# NanoBase_L293D_DBL.net
KiCad netlist of a schematic drawn in EAGLE
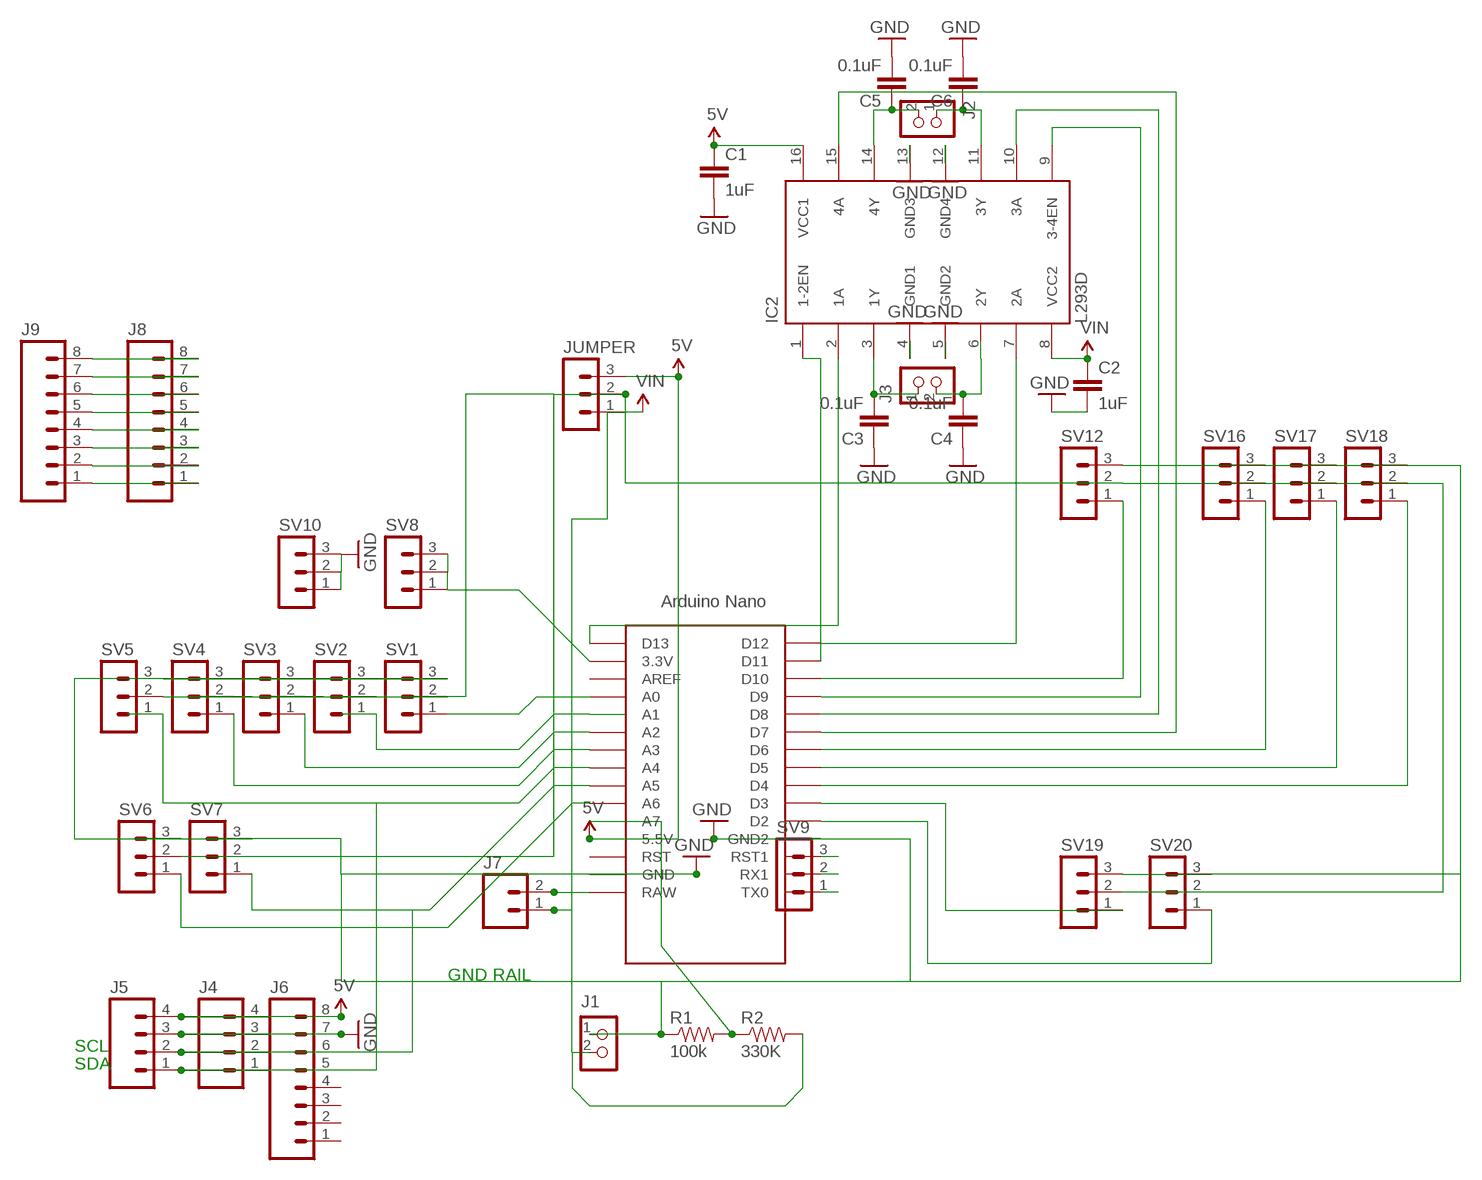
[diagram p0: schematic, sheet 1]

(export (version "E")
  (design (tool "Eeschema 10.0.6"))
  (components
    (comp (ref "C1")
      (value "1uF")
      (footprint "eagle-import:1206")
      (libsource (lib "eagle-import") (part "2.2UF-CERCAP-10009"))
    )
    (comp (ref "C2")
      (value "1uF")
      (footprint "eagle-import:1206")
      (libsource (lib "eagle-import") (part "2.2UF-CERCAP-10009"))
    )
    (comp (ref "C3")
      (value "0.1uF")
      (footprint "eagle-import:1206")
      (libsource (lib "eagle-import") (part "2.2UF-CERCAP-10009"))
    )
    (comp (ref "C4")
      (value "0.1uF")
      (footprint "eagle-import:1206")
      (libsource (lib "eagle-import") (part "2.2UF-CERCAP-10009"))
    )
    (comp (ref "C5")
      (value "0.1uF")
      (footprint "eagle-import:1206")
      (libsource (lib "eagle-import") (part "2.2UF-CERCAP-10009"))
    )
    (comp (ref "C6")
      (value "0.1uF")
      (footprint "eagle-import:1206")
      (libsource (lib "eagle-import") (part "2.2UF-CERCAP-10009"))
    )
    (comp (ref "IC2")
      (value "L293D")
      (footprint "eagle-import:DIL16")
      (libsource (lib "eagle-import") (part "L293D"))
    )
    (comp (ref "J1")
      (value "CON_TERMINAL_BLOCK_02-5MM")
      (footprint "eagle-import:TERMINAL_BLOCK_2P_5")
      (libsource (lib "eagle-import") (part "CON_TERMINAL_BLOCK_02-5MM"))
    )
    (comp (ref "J2")
      (value "CON_TERMINAL_BLOCK_02-5MM")
      (footprint "eagle-import:TERMINAL_BLOCK_2P_5")
      (libsource (lib "eagle-import") (part "CON_TERMINAL_BLOCK_02-5MM"))
    )
    (comp (ref "J3")
      (value "CON_TERMINAL_BLOCK_02-5MM")
      (footprint "eagle-import:TERMINAL_BLOCK_2P_5")
      (libsource (lib "eagle-import") (part "CON_TERMINAL_BLOCK_02-5MM"))
    )
    (comp (ref "J4")
      (value "M04LOCK")
      (footprint "eagle-import:1X04_LOCK")
      (libsource (lib "eagle-import") (part "M04LOCK"))
    )
    (comp (ref "J5")
      (value "M04LOCK")
      (footprint "eagle-import:1X04_LOCK")
      (libsource (lib "eagle-import") (part "M04LOCK"))
    )
    (comp (ref "J6")
      (value "M08NO_SILK")
      (footprint "eagle-import:1X08_PIN1_NO_SILK")
      (libsource (lib "eagle-import") (part "M08NO_SILK"))
    )
    (comp (ref "J7")
      (value "M02LOCK_LONGPADS")
      (footprint "eagle-import:1X02_LOCK_LONGPADS")
      (libsource (lib "eagle-import") (part "M02LOCK_LONGPADS"))
    )
    (comp (ref "J8")
      (value "M08NO_SILK")
      (footprint "eagle-import:1X08_PIN1_NO_SILK")
      (libsource (lib "eagle-import") (part "M08NO_SILK"))
    )
    (comp (ref "J9")
      (value "M08NO_SILK")
      (footprint "eagle-import:1X08_PIN1_NO_SILK")
      (libsource (lib "eagle-import") (part "M08NO_SILK"))
    )
    (comp (ref "JUMPER")
      (value "MA03-1")
      (footprint "eagle-import:MA03-1")
      (libsource (lib "eagle-import") (part "MA03-1"))
    )
    (comp (ref "R1")
      (value "100k")
      (footprint "eagle-import:1206")
      (libsource (lib "eagle-import") (part "RESISTOR1206"))
    )
    (comp (ref "R2")
      (value "330K")
      (footprint "eagle-import:1206")
      (libsource (lib "eagle-import") (part "RESISTOR1206"))
    )
    (comp (ref "SV1")
      (value "MA03-1")
      (footprint "eagle-import:MA03-1")
      (libsource (lib "eagle-import") (part "MA03-1"))
    )
    (comp (ref "SV2")
      (value "MA03-1")
      (footprint "eagle-import:MA03-1")
      (libsource (lib "eagle-import") (part "MA03-1"))
    )
    (comp (ref "SV3")
      (value "MA03-1")
      (footprint "eagle-import:MA03-1")
      (libsource (lib "eagle-import") (part "MA03-1"))
    )
    (comp (ref "SV4")
      (value "MA03-1")
      (footprint "eagle-import:MA03-1")
      (libsource (lib "eagle-import") (part "MA03-1"))
    )
    (comp (ref "SV5")
      (value "MA03-1")
      (footprint "eagle-import:MA03-1")
      (libsource (lib "eagle-import") (part "MA03-1"))
    )
    (comp (ref "SV6")
      (value "MA03-1")
      (footprint "eagle-import:MA03-1")
      (libsource (lib "eagle-import") (part "MA03-1"))
    )
    (comp (ref "SV7")
      (value "MA03-1")
      (footprint "eagle-import:MA03-1")
      (libsource (lib "eagle-import") (part "MA03-1"))
    )
    (comp (ref "SV8")
      (value "MA03-1")
      (footprint "eagle-import:MA03-1")
      (libsource (lib "eagle-import") (part "MA03-1"))
    )
    (comp (ref "SV9")
      (value "MA03-1")
      (footprint "eagle-import:MA03-1")
      (libsource (lib "eagle-import") (part "MA03-1"))
    )
    (comp (ref "SV10")
      (value "MA03-1")
      (footprint "eagle-import:MA03-1")
      (libsource (lib "eagle-import") (part "MA03-1"))
    )
    (comp (ref "SV12")
      (value "MA03-1")
      (footprint "eagle-import:MA03-1")
      (libsource (lib "eagle-import") (part "MA03-1"))
    )
    (comp (ref "SV16")
      (value "MA03-1")
      (footprint "eagle-import:MA03-1")
      (libsource (lib "eagle-import") (part "MA03-1"))
    )
    (comp (ref "SV17")
      (value "MA03-1")
      (footprint "eagle-import:MA03-1")
      (libsource (lib "eagle-import") (part "MA03-1"))
    )
    (comp (ref "SV18")
      (value "MA03-1")
      (footprint "eagle-import:MA03-1")
      (libsource (lib "eagle-import") (part "MA03-1"))
    )
    (comp (ref "SV19")
      (value "MA03-1")
      (footprint "eagle-import:MA03-1")
      (libsource (lib "eagle-import") (part "MA03-1"))
    )
    (comp (ref "SV20")
      (value "MA03-1")
      (footprint "eagle-import:MA03-1")
      (libsource (lib "eagle-import") (part "MA03-1"))
    )
    (comp (ref "U$1")
      (value "NANO")
      (footprint "eagle-import:NANO")
      (libsource (lib "eagle-import") (part "NANO"))
    )
  )
  (nets
    (net (code "1") (name "5V") (class "Default")
      (node (ref "C1") (pin "1") (pinfunction "1_1") (pintype "passive"))
      (node (ref "IC2") (pin "16") (pinfunction "VCC1_16") (pintype "power_in"))
      (node (ref "J4") (pin "4") (pinfunction "4_4") (pintype "passive"))
      (node (ref "J5") (pin "4") (pinfunction "4_4") (pintype "passive"))
      (node (ref "J6") (pin "8") (pinfunction "8_8") (pintype "passive"))
      (node (ref "JUMPER") (pin "3") (pinfunction "3_3") (pintype "passive"))
      (node (ref "U$1") (pin "5V") (pinfunction "5.5V_5V") (pintype "bidirectional"))
    )
    (net (code "2") (name "GND") (class "Default")
      (node (ref "C1") (pin "2") (pinfunction "2_2") (pintype "passive"))
      (node (ref "C2") (pin "2") (pinfunction "2_2") (pintype "passive"))
      (node (ref "C3") (pin "1") (pinfunction "1_1") (pintype "passive"))
      (node (ref "C4") (pin "1") (pinfunction "1_1") (pintype "passive"))
      (node (ref "C5") (pin "2") (pinfunction "2_2") (pintype "passive"))
      (node (ref "C6") (pin "2") (pinfunction "2_2") (pintype "passive"))
      (node (ref "IC2") (pin "12") (pinfunction "GND4_12") (pintype "power_in"))
      (node (ref "IC2") (pin "13") (pinfunction "GND3_13") (pintype "power_in"))
      (node (ref "IC2") (pin "4") (pinfunction "GND1_4") (pintype "power_in"))
      (node (ref "IC2") (pin "5") (pinfunction "GND2_5") (pintype "power_in"))
      (node (ref "J1") (pin "1") (pinfunction "1_1") (pintype "passive"))
      (node (ref "J4") (pin "3") (pinfunction "3_3") (pintype "passive"))
      (node (ref "J5") (pin "3") (pinfunction "3_3") (pintype "passive"))
      (node (ref "J6") (pin "7") (pinfunction "7_7") (pintype "passive"))
      (node (ref "R1") (pin "1") (pinfunction "1_1") (pintype "passive"))
      (node (ref "SV1") (pin "3") (pinfunction "3_3") (pintype "passive"))
      (node (ref "SV10") (pin "1") (pinfunction "1_1") (pintype "passive"))
      (node (ref "SV10") (pin "2") (pinfunction "2_2") (pintype "passive"))
      (node (ref "SV10") (pin "3") (pinfunction "3_3") (pintype "passive"))
      (node (ref "SV12") (pin "3") (pinfunction "3_3") (pintype "passive"))
      (node (ref "SV16") (pin "3") (pinfunction "3_3") (pintype "passive"))
      (node (ref "SV17") (pin "3") (pinfunction "3_3") (pintype "passive"))
      (node (ref "SV18") (pin "3") (pinfunction "3_3") (pintype "passive"))
      (node (ref "SV19") (pin "3") (pinfunction "3_3") (pintype "passive"))
      (node (ref "SV2") (pin "3") (pinfunction "3_3") (pintype "passive"))
      (node (ref "SV20") (pin "3") (pinfunction "3_3") (pintype "passive"))
      (node (ref "SV3") (pin "3") (pinfunction "3_3") (pintype "passive"))
      (node (ref "SV4") (pin "3") (pinfunction "3_3") (pintype "passive"))
      (node (ref "SV5") (pin "3") (pinfunction "3_3") (pintype "passive"))
      (node (ref "SV6") (pin "3") (pinfunction "3_3") (pintype "passive"))
      (node (ref "SV7") (pin "3") (pinfunction "3_3") (pintype "passive"))
      (node (ref "U$1") (pin "GND") (pinfunction "GND_GND") (pintype "bidirectional"))
      (node (ref "U$1") (pin "GND1") (pinfunction "GND2_GND1") (pintype "bidirectional"))
    )
    (net (code "3") (name "Net-(IC2-1-2EN)") (class "Default")
      (node (ref "IC2") (pin "1") (pinfunction "1-2EN_1") (pintype "input"))
      (node (ref "U$1") (pin "D11") (pinfunction "D11_D11") (pintype "bidirectional"))
    )
    (net (code "4") (name "Net-(IC2-1A)") (class "Default")
      (node (ref "IC2") (pin "2") (pinfunction "1A_2") (pintype "input"))
      (node (ref "U$1") (pin "D13") (pinfunction "D13_D13") (pintype "bidirectional"))
    )
    (net (code "5") (name "Net-(IC2-1Y)") (class "Default")
      (node (ref "C3") (pin "2") (pinfunction "2_2") (pintype "passive"))
      (node (ref "IC2") (pin "3") (pinfunction "1Y_3") (pintype "output"))
      (node (ref "J3") (pin "1") (pinfunction "1_1") (pintype "passive"))
    )
    (net (code "6") (name "Net-(IC2-2A)") (class "Default")
      (node (ref "IC2") (pin "7") (pinfunction "2A_7") (pintype "input"))
      (node (ref "U$1") (pin "D12") (pinfunction "D12_D12") (pintype "bidirectional"))
    )
    (net (code "7") (name "Net-(IC2-2Y)") (class "Default")
      (node (ref "C4") (pin "2") (pinfunction "2_2") (pintype "passive"))
      (node (ref "IC2") (pin "6") (pinfunction "2Y_6") (pintype "output"))
      (node (ref "J3") (pin "2") (pinfunction "2_2") (pintype "passive"))
    )
    (net (code "8") (name "Net-(IC2-3-4EN)") (class "Default")
      (node (ref "IC2") (pin "9") (pinfunction "3-4EN_9") (pintype "input"))
      (node (ref "U$1") (pin "D9") (pinfunction "D9_D9") (pintype "bidirectional"))
    )
    (net (code "9") (name "Net-(IC2-3A)") (class "Default")
      (node (ref "IC2") (pin "10") (pinfunction "3A_10") (pintype "input"))
      (node (ref "U$1") (pin "D8") (pinfunction "D8_D8") (pintype "bidirectional"))
    )
    (net (code "10") (name "Net-(IC2-3Y)") (class "Default")
      (node (ref "C6") (pin "1") (pinfunction "1_1") (pintype "passive"))
      (node (ref "IC2") (pin "11") (pinfunction "3Y_11") (pintype "output"))
      (node (ref "J2") (pin "1") (pinfunction "1_1") (pintype "passive"))
    )
    (net (code "11") (name "Net-(IC2-4A)") (class "Default")
      (node (ref "IC2") (pin "15") (pinfunction "4A_15") (pintype "input"))
      (node (ref "U$1") (pin "D7") (pinfunction "D7_D7") (pintype "bidirectional"))
    )
    (net (code "12") (name "Net-(IC2-4Y)") (class "Default")
      (node (ref "C5") (pin "1") (pinfunction "1_1") (pintype "passive"))
      (node (ref "IC2") (pin "14") (pinfunction "4Y_14") (pintype "output"))
      (node (ref "J2") (pin "2") (pinfunction "2_2") (pintype "passive"))
    )
    (net (code "13") (name "Net-(J4-Pad1)") (class "Default")
      (node (ref "J4") (pin "1") (pinfunction "1_1") (pintype "passive"))
      (node (ref "J5") (pin "1") (pinfunction "1_1") (pintype "passive"))
      (node (ref "J6") (pin "5") (pinfunction "5_5") (pintype "passive"))
      (node (ref "SV5") (pin "1") (pinfunction "1_1") (pintype "passive"))
      (node (ref "U$1") (pin "A4") (pinfunction "A4_A4") (pintype "bidirectional"))
    )
    (net (code "14") (name "Net-(J4-Pad2)") (class "Default")
      (node (ref "J4") (pin "2") (pinfunction "2_2") (pintype "passive"))
      (node (ref "J5") (pin "2") (pinfunction "2_2") (pintype "passive"))
      (node (ref "J6") (pin "6") (pinfunction "6_6") (pintype "passive"))
      (node (ref "SV7") (pin "1") (pinfunction "1_1") (pintype "passive"))
      (node (ref "U$1") (pin "A5") (pinfunction "A5_A5") (pintype "bidirectional"))
    )
    (net (code "15") (name "Net-(J7-Pad2)") (class "Default")
      (node (ref "J7") (pin "2") (pinfunction "2_2") (pintype "passive"))
      (node (ref "U$1") (pin "RAW") (pinfunction "RAW_RAW") (pintype "bidirectional"))
    )
    (net (code "16") (name "Net-(J8-Pad1)") (class "Default")
      (node (ref "J8") (pin "1") (pinfunction "1_1") (pintype "passive"))
      (node (ref "J9") (pin "1") (pinfunction "1_1") (pintype "passive"))
    )
    (net (code "17") (name "Net-(J8-Pad2)") (class "Default")
      (node (ref "J8") (pin "2") (pinfunction "2_2") (pintype "passive"))
      (node (ref "J9") (pin "2") (pinfunction "2_2") (pintype "passive"))
    )
    (net (code "18") (name "Net-(J8-Pad3)") (class "Default")
      (node (ref "J8") (pin "3") (pinfunction "3_3") (pintype "passive"))
      (node (ref "J9") (pin "3") (pinfunction "3_3") (pintype "passive"))
    )
    (net (code "19") (name "Net-(J8-Pad4)") (class "Default")
      (node (ref "J8") (pin "4") (pinfunction "4_4") (pintype "passive"))
      (node (ref "J9") (pin "4") (pinfunction "4_4") (pintype "passive"))
    )
    (net (code "20") (name "Net-(J8-Pad5)") (class "Default")
      (node (ref "J8") (pin "5") (pinfunction "5_5") (pintype "passive"))
      (node (ref "J9") (pin "5") (pinfunction "5_5") (pintype "passive"))
    )
    (net (code "21") (name "Net-(J8-Pad6)") (class "Default")
      (node (ref "J8") (pin "6") (pinfunction "6_6") (pintype "passive"))
      (node (ref "J9") (pin "6") (pinfunction "6_6") (pintype "passive"))
    )
    (net (code "22") (name "Net-(J8-Pad7)") (class "Default")
      (node (ref "J8") (pin "7") (pinfunction "7_7") (pintype "passive"))
      (node (ref "J9") (pin "7") (pinfunction "7_7") (pintype "passive"))
    )
    (net (code "23") (name "Net-(J8-Pad8)") (class "Default")
      (node (ref "J8") (pin "8") (pinfunction "8_8") (pintype "passive"))
      (node (ref "J9") (pin "8") (pinfunction "8_8") (pintype "passive"))
    )
    (net (code "24") (name "Net-(JUMPER-Pad2)") (class "Default")
      (node (ref "JUMPER") (pin "2") (pinfunction "2_2") (pintype "passive"))
      (node (ref "SV1") (pin "2") (pinfunction "2_2") (pintype "passive"))
      (node (ref "SV12") (pin "2") (pinfunction "2_2") (pintype "passive"))
      (node (ref "SV16") (pin "2") (pinfunction "2_2") (pintype "passive"))
      (node (ref "SV17") (pin "2") (pinfunction "2_2") (pintype "passive"))
      (node (ref "SV18") (pin "2") (pinfunction "2_2") (pintype "passive"))
      (node (ref "SV19") (pin "2") (pinfunction "2_2") (pintype "passive"))
      (node (ref "SV2") (pin "2") (pinfunction "2_2") (pintype "passive"))
      (node (ref "SV20") (pin "2") (pinfunction "2_2") (pintype "passive"))
      (node (ref "SV3") (pin "2") (pinfunction "2_2") (pintype "passive"))
      (node (ref "SV4") (pin "2") (pinfunction "2_2") (pintype "passive"))
      (node (ref "SV5") (pin "2") (pinfunction "2_2") (pintype "passive"))
      (node (ref "SV6") (pin "2") (pinfunction "2_2") (pintype "passive"))
      (node (ref "SV7") (pin "2") (pinfunction "2_2") (pintype "passive"))
    )
    (net (code "25") (name "Net-(R1-Pad2)") (class "Default")
      (node (ref "R1") (pin "2") (pinfunction "2_2") (pintype "passive"))
      (node (ref "R2") (pin "1") (pinfunction "1_1") (pintype "passive"))
      (node (ref "U$1") (pin "A7") (pinfunction "A7_A7") (pintype "bidirectional"))
    )
    (net (code "26") (name "Net-(SV1-Pad1)") (class "Default")
      (node (ref "SV1") (pin "1") (pinfunction "1_1") (pintype "passive"))
      (node (ref "U$1") (pin "A0") (pinfunction "A0_A0") (pintype "bidirectional"))
    )
    (net (code "27") (name "Net-(SV2-Pad1)") (class "Default")
      (node (ref "SV2") (pin "1") (pinfunction "1_1") (pintype "passive"))
      (node (ref "U$1") (pin "A1") (pinfunction "A1_A1") (pintype "bidirectional"))
    )
    (net (code "28") (name "Net-(SV3-Pad1)") (class "Default")
      (node (ref "SV3") (pin "1") (pinfunction "1_1") (pintype "passive"))
      (node (ref "U$1") (pin "A2") (pinfunction "A2_A2") (pintype "bidirectional"))
    )
    (net (code "29") (name "Net-(SV4-Pad1)") (class "Default")
      (node (ref "SV4") (pin "1") (pinfunction "1_1") (pintype "passive"))
      (node (ref "U$1") (pin "A3") (pinfunction "A3_A3") (pintype "bidirectional"))
    )
    (net (code "30") (name "Net-(SV6-Pad1)") (class "Default")
      (node (ref "SV6") (pin "1") (pinfunction "1_1") (pintype "passive"))
      (node (ref "U$1") (pin "A6") (pinfunction "A6_A6") (pintype "bidirectional"))
    )
    (net (code "31") (name "Net-(SV8-Pad1)") (class "Default")
      (node (ref "SV8") (pin "1") (pinfunction "1_1") (pintype "passive"))
      (node (ref "SV8") (pin "2") (pinfunction "2_2") (pintype "passive"))
      (node (ref "SV8") (pin "3") (pinfunction "3_3") (pintype "passive"))
      (node (ref "U$1") (pin "3.3V") (pinfunction "3.3V_3.3V") (pintype "bidirectional"))
    )
    (net (code "32") (name "Net-(SV9-Pad1)") (class "Default")
      (node (ref "SV9") (pin "1") (pinfunction "1_1") (pintype "passive"))
      (node (ref "U$1") (pin "TX0") (pinfunction "TX0_TX0") (pintype "bidirectional"))
    )
    (net (code "33") (name "Net-(SV9-Pad2)") (class "Default")
      (node (ref "SV9") (pin "2") (pinfunction "2_2") (pintype "passive"))
      (node (ref "U$1") (pin "RX1") (pinfunction "RX1_RX1") (pintype "bidirectional"))
    )
    (net (code "34") (name "Net-(SV9-Pad3)") (class "Default")
      (node (ref "SV9") (pin "3") (pinfunction "3_3") (pintype "passive"))
      (node (ref "U$1") (pin "RST1") (pinfunction "RST1_RST1") (pintype "bidirectional"))
    )
    (net (code "35") (name "Net-(SV12-Pad1)") (class "Default")
      (node (ref "SV12") (pin "1") (pinfunction "1_1") (pintype "passive"))
      (node (ref "U$1") (pin "D10") (pinfunction "D10_D10") (pintype "bidirectional"))
    )
    (net (code "36") (name "Net-(SV16-Pad1)") (class "Default")
      (node (ref "SV16") (pin "1") (pinfunction "1_1") (pintype "passive"))
      (node (ref "U$1") (pin "D6") (pinfunction "D6_D6") (pintype "bidirectional"))
    )
    (net (code "37") (name "Net-(SV17-Pad1)") (class "Default")
      (node (ref "SV17") (pin "1") (pinfunction "1_1") (pintype "passive"))
      (node (ref "U$1") (pin "D5") (pinfunction "D5_D5") (pintype "bidirectional"))
    )
    (net (code "38") (name "Net-(SV18-Pad1)") (class "Default")
      (node (ref "SV18") (pin "1") (pinfunction "1_1") (pintype "passive"))
      (node (ref "U$1") (pin "D4") (pinfunction "D4_D4") (pintype "bidirectional"))
    )
    (net (code "39") (name "Net-(SV19-Pad1)") (class "Default")
      (node (ref "SV19") (pin "1") (pinfunction "1_1") (pintype "passive"))
      (node (ref "U$1") (pin "D3") (pinfunction "D3_D3") (pintype "bidirectional"))
    )
    (net (code "40") (name "Net-(SV20-Pad1)") (class "Default")
      (node (ref "SV20") (pin "1") (pinfunction "1_1") (pintype "passive"))
      (node (ref "U$1") (pin "D2") (pinfunction "D2_D2") (pintype "bidirectional"))
    )
    (net (code "41") (name "VIN") (class "Default")
      (node (ref "C2") (pin "1") (pinfunction "1_1") (pintype "passive"))
      (node (ref "IC2") (pin "8") (pinfunction "VCC2_8") (pintype "power_in"))
      (node (ref "J1") (pin "2") (pinfunction "2_2") (pintype "passive"))
      (node (ref "J7") (pin "1") (pinfunction "1_1") (pintype "passive"))
      (node (ref "JUMPER") (pin "1") (pinfunction "1_1") (pintype "passive"))
      (node (ref "R2") (pin "2") (pinfunction "2_2") (pintype "passive"))
    )
    (net (code "42") (name "unconnected-(J6-Pad1)") (class "Default")
      (node (ref "J6") (pin "1") (pinfunction "1_1") (pintype "passive"))
    )
    (net (code "43") (name "unconnected-(J6-Pad2)") (class "Default")
      (node (ref "J6") (pin "2") (pinfunction "2_2") (pintype "passive"))
    )
    (net (code "44") (name "unconnected-(J6-Pad3)") (class "Default")
      (node (ref "J6") (pin "3") (pinfunction "3_3") (pintype "passive"))
    )
    (net (code "45") (name "unconnected-(J6-Pad4)") (class "Default")
      (node (ref "J6") (pin "4") (pinfunction "4_4") (pintype "passive"))
    )
    (net (code "46") (name "unconnected-(U$1-PadAREF)") (class "Default")
      (node (ref "U$1") (pin "AREF") (pinfunction "AREF_AREF") (pintype "bidirectional"))
    )
    (net (code "47") (name "unconnected-(U$1-PadICSP1)") (class "Default")
      (node (ref "U$1") (pin "ICSP1") (pinfunction "ICSP1_ICSP1") (pintype "bidirectional"))
    )
    (net (code "48") (name "unconnected-(U$1-PadICSP2)") (class "Default")
      (node (ref "U$1") (pin "ICSP2") (pinfunction "ICSP2_ICSP2") (pintype "bidirectional"))
    )
    (net (code "49") (name "unconnected-(U$1-PadICSP3)") (class "Default")
      (node (ref "U$1") (pin "ICSP3") (pinfunction "ICSP3_ICSP3") (pintype "bidirectional"))
    )
    (net (code "50") (name "unconnected-(U$1-PadICSP4)") (class "Default")
      (node (ref "U$1") (pin "ICSP4") (pinfunction "ICSP4_ICSP4") (pintype "bidirectional"))
    )
    (net (code "51") (name "unconnected-(U$1-PadICSP5)") (class "Default")
      (node (ref "U$1") (pin "ICSP5") (pinfunction "ICSP5_ICSP5") (pintype "bidirectional"))
    )
    (net (code "52") (name "unconnected-(U$1-PadICSP6)") (class "Default")
      (node (ref "U$1") (pin "ICSP6") (pinfunction "ICSP6_ICSP6") (pintype "bidirectional"))
    )
    (net (code "53") (name "unconnected-(U$1-PadRST)") (class "Default")
      (node (ref "U$1") (pin "RST") (pinfunction "RST_RST") (pintype "bidirectional"))
    )
  )
)
